# CLK_SYNTH_V2_4.net
KiCad netlist of a schematic drawn in Altium Designer
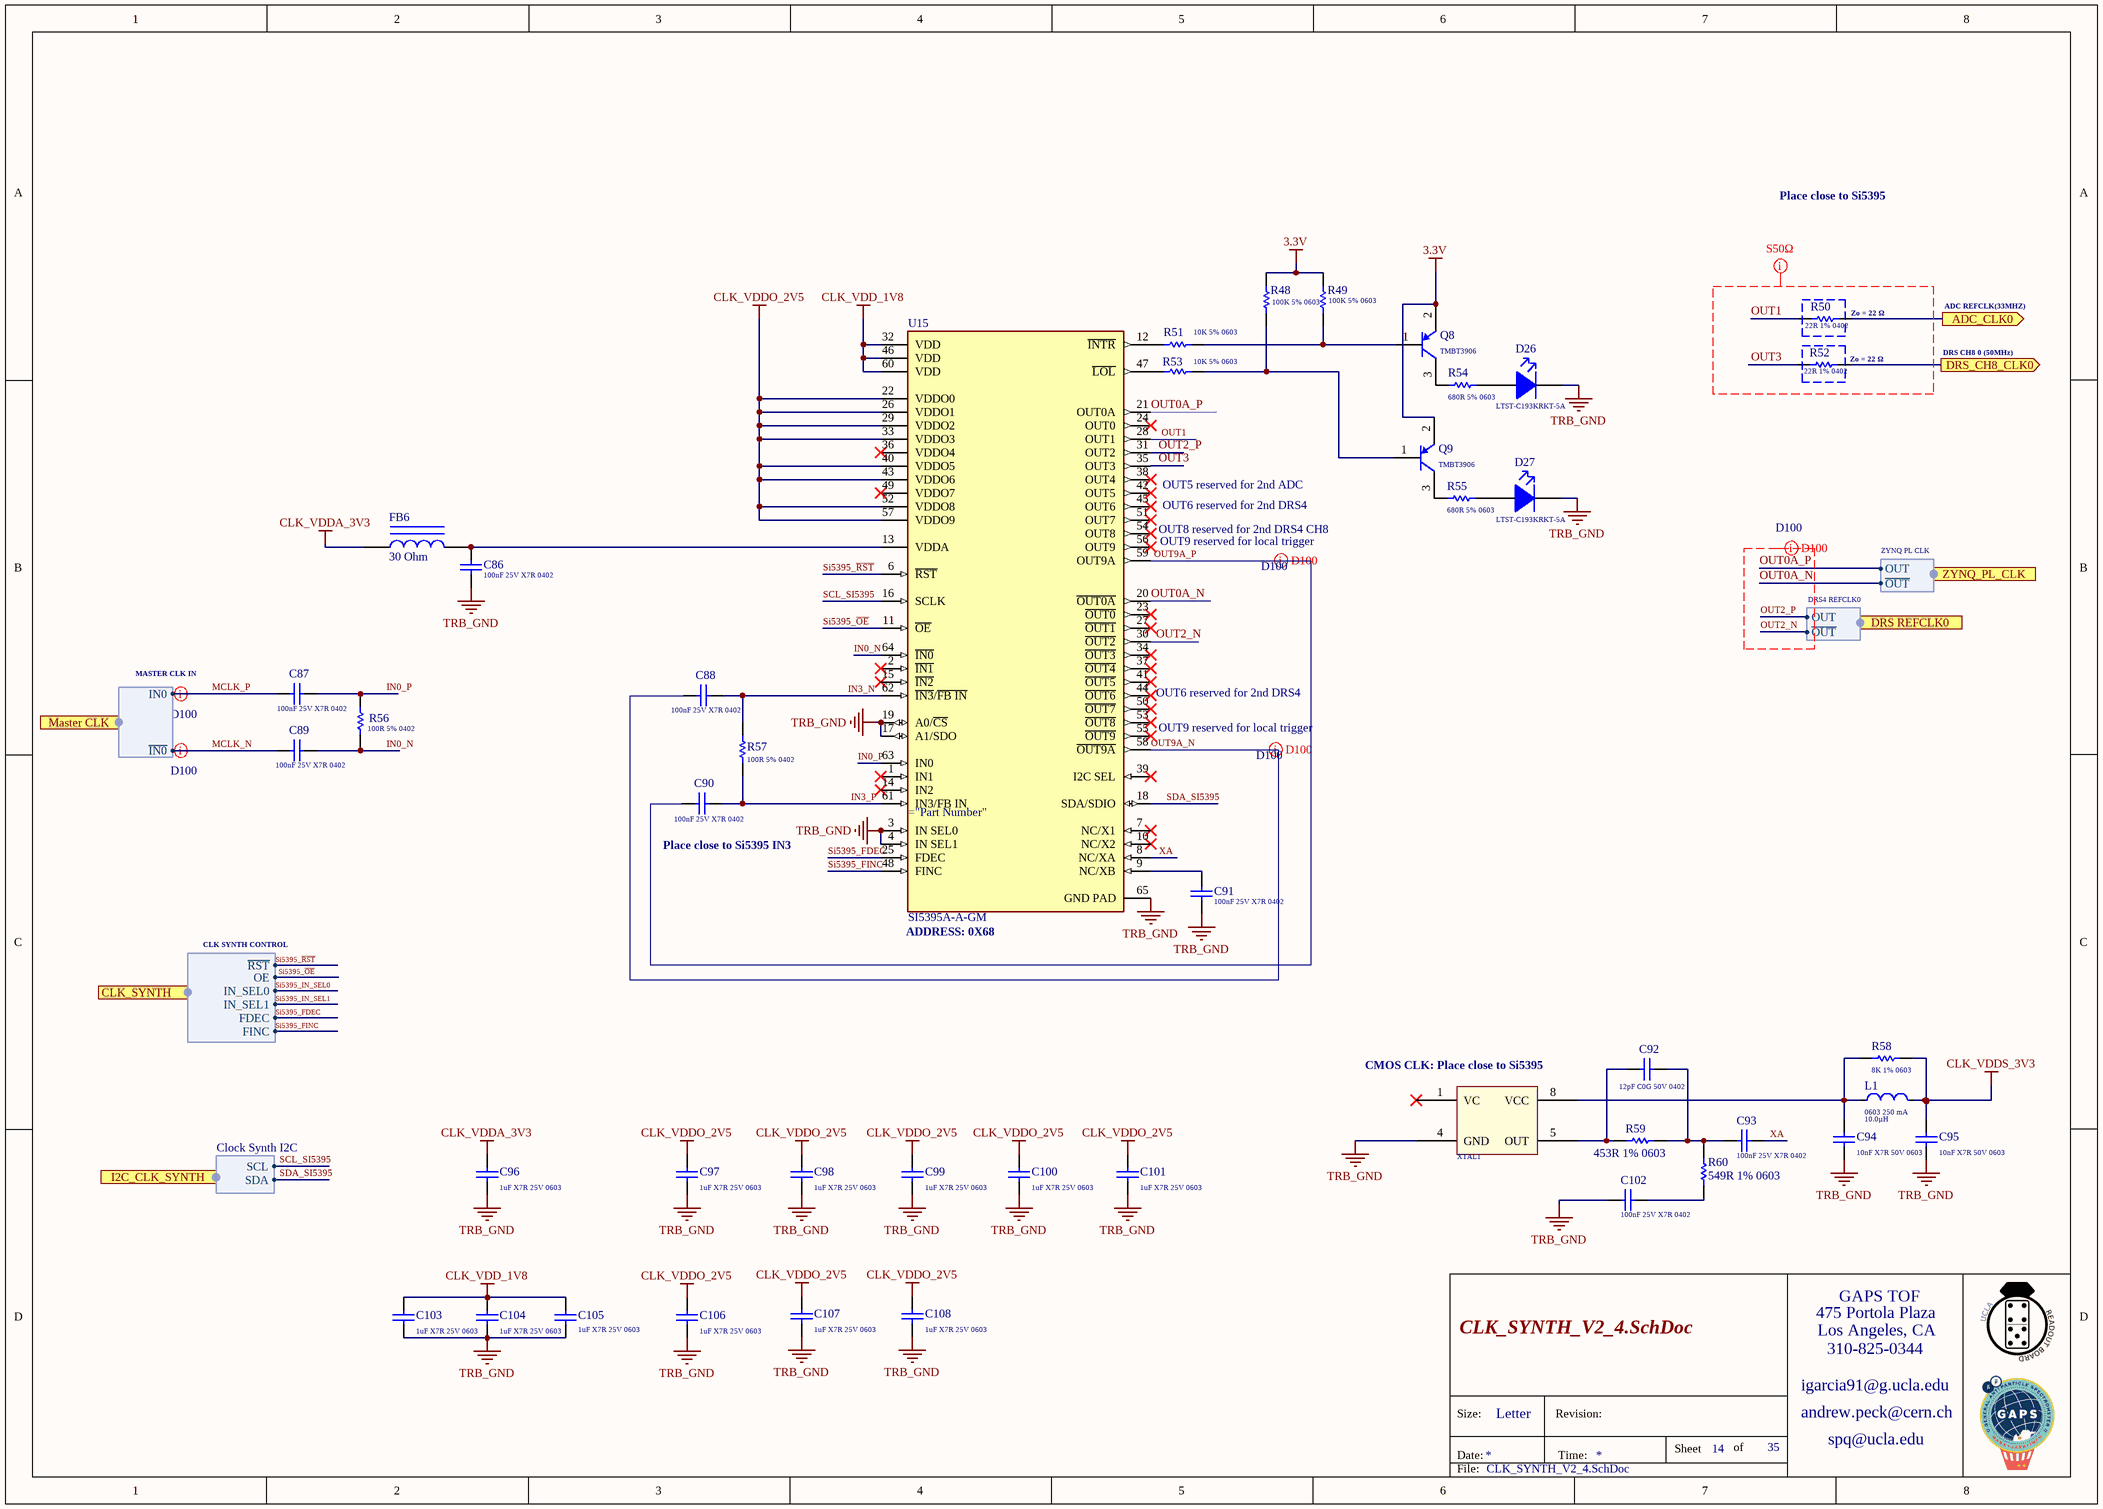
[diagram p0: CLK_SYNTH_V2_4.SchDoc]

(export (version "E")
  (design (tool "Eeschema 10.0.6"))
  (components
    (comp (ref "C86")
      (value "Cap_Taiyo_Yuden_TMK105B7104KV-FR_100nF")
      (footprint "Cap_Taiyo_Yuden_TMK105B7104KV-FR_100nF")
      (description "CAP CER 100nF 25V X7R 0402")
      (fields (field (name "CAPACITANCE") "100nF 25V X7R 0402"))
      (libsource (lib "Cap_Taiyo_Yuden_TMK105B7104KV-FR_100nF") (part "Cap_Taiyo_Yuden_TMK105B7104KV-FR_100nF"))
    )
    (comp (ref "C87")
      (value "Cap_Taiyo_Yuden_TMK105B7104KV-FR_100nF")
      (footprint "Cap_Taiyo_Yuden_TMK105B7104KV-FR_100nF")
      (description "CAP CER 100nF 25V X7R 0402")
      (fields (field (name "CAPACITANCE") "100nF 25V X7R 0402"))
      (libsource (lib "Cap_Taiyo_Yuden_TMK105B7104KV-FR_100nF") (part "Cap_Taiyo_Yuden_TMK105B7104KV-FR_100nF"))
    )
    (comp (ref "C88")
      (value "Cap_Taiyo_Yuden_TMK105B7104KV-FR_100nF")
      (footprint "Cap_Taiyo_Yuden_TMK105B7104KV-FR_100nF")
      (description "CAP CER 100nF 25V X7R 0402")
      (fields (field (name "CAPACITANCE") "100nF 25V X7R 0402"))
      (libsource (lib "Cap_Taiyo_Yuden_TMK105B7104KV-FR_100nF") (part "Cap_Taiyo_Yuden_TMK105B7104KV-FR_100nF"))
    )
    (comp (ref "C89")
      (value "Cap_Taiyo_Yuden_TMK105B7104KV-FR_100nF")
      (footprint "Cap_Taiyo_Yuden_TMK105B7104KV-FR_100nF")
      (description "CAP CER 100nF 25V X7R 0402")
      (fields (field (name "CAPACITANCE") "100nF 25V X7R 0402"))
      (libsource (lib "Cap_Taiyo_Yuden_TMK105B7104KV-FR_100nF") (part "Cap_Taiyo_Yuden_TMK105B7104KV-FR_100nF"))
    )
    (comp (ref "C90")
      (value "Cap_Taiyo_Yuden_TMK105B7104KV-FR_100nF")
      (footprint "Cap_Taiyo_Yuden_TMK105B7104KV-FR_100nF")
      (description "CAP CER 100nF 25V X7R 0402")
      (fields (field (name "CAPACITANCE") "100nF 25V X7R 0402"))
      (libsource (lib "Cap_Taiyo_Yuden_TMK105B7104KV-FR_100nF") (part "Cap_Taiyo_Yuden_TMK105B7104KV-FR_100nF"))
    )
    (comp (ref "C91")
      (value "Cap_Taiyo_Yuden_TMK105B7104KV-FR_100nF")
      (footprint "Cap_Taiyo_Yuden_TMK105B7104KV-FR_100nF")
      (description "CAP CER 100nF 25V X7R 0402")
      (fields (field (name "CAPACITANCE") "100nF 25V X7R 0402"))
      (libsource (lib "Cap_Taiyo_Yuden_TMK105B7104KV-FR_100nF") (part "Cap_Taiyo_Yuden_TMK105B7104KV-FR_100nF"))
    )
    (comp (ref "C92")
      (value "Cap_Murata_GCQ1555C1H120FB01D_12pF")
      (footprint "Cap_Murata_GCQ1555C1H120FB01D_12pF")
      (description "MLCC - SMD/SMT 0402 50VDC 12pF 1% AEC-Q200")
      (fields (field (name "CAPACITANCE") "12pF C0G 50V 0402"))
      (libsource (lib "Cap_Murata_GCQ1555C1H120FB01D_12pF") (part "Cap_Murata_GCQ1555C1H120FB01D_12pF"))
    )
    (comp (ref "C93")
      (value "Cap_Taiyo_Yuden_TMK105B7104KV-FR_100nF")
      (footprint "Cap_Taiyo_Yuden_TMK105B7104KV-FR_100nF")
      (description "CAP CER 100nF 25V X7R 0402")
      (fields (field (name "CAPACITANCE") "100nF 25V X7R 0402"))
      (libsource (lib "Cap_Taiyo_Yuden_TMK105B7104KV-FR_100nF") (part "Cap_Taiyo_Yuden_TMK105B7104KV-FR_100nF"))
    )
    (comp (ref "C94")
      (value "Cap_Kemet_C0603C103J5RACTU_eec")
      (footprint "Kemet_C0603_0")
      (description "CAP CER 10nF 50V X7R 0603")
      (fields
        (field (name "PART NUMBER") "C0603C103J5RACTU")
        (field (name "MANUFACTURER") "Kemet")
        (field (name "CAPACITANCE") "10nF X7R 50V 0603")
      )
      (libsource (lib "Cap_Kemet_C0603C103J5RACTU_10nF") (part "Cap_Kemet_C0603C103J5RACTU_eec"))
    )
    (comp (ref "C95")
      (value "Cap_Kemet_C0603C103J5RACTU_eec")
      (footprint "Kemet_C0603_0")
      (description "CAP CER 10nF 50V X7R 0603")
      (fields
        (field (name "PART NUMBER") "C0603C103J5RACTU")
        (field (name "MANUFACTURER") "Kemet")
        (field (name "CAPACITANCE") "10nF X7R 50V 0603")
      )
      (libsource (lib "Cap_Kemet_C0603C103J5RACTU_10nF") (part "Cap_Kemet_C0603C103J5RACTU_eec"))
    )
    (comp (ref "C96")
      (value "Cap_Murata_GCJ188R71E105KA01J_1uF")
      (footprint "Cap_Murata_GCJ188R71E105KA01J_1uF")
      (description "CAP CER 1uF 25V X7R 0603")
      (fields (field (name "CAPACITANCE") "1uF X7R 25V 0603"))
      (libsource (lib "Cap_Murata_GCJ188R71E105KA01J_1uF") (part "Cap_Murata_GCJ188R71E105KA01J_1uF"))
    )
    (comp (ref "C97")
      (value "Cap_Murata_GCJ188R71E105KA01J_1uF")
      (footprint "Cap_Murata_GCJ188R71E105KA01J_1uF")
      (description "CAP CER 1uF 25V X7R 0603")
      (fields (field (name "CAPACITANCE") "1uF X7R 25V 0603"))
      (libsource (lib "Cap_Murata_GCJ188R71E105KA01J_1uF") (part "Cap_Murata_GCJ188R71E105KA01J_1uF"))
    )
    (comp (ref "C98")
      (value "Cap_Murata_GCJ188R71E105KA01J_1uF")
      (footprint "Cap_Murata_GCJ188R71E105KA01J_1uF")
      (description "CAP CER 1uF 25V X7R 0603")
      (fields (field (name "CAPACITANCE") "1uF X7R 25V 0603"))
      (libsource (lib "Cap_Murata_GCJ188R71E105KA01J_1uF") (part "Cap_Murata_GCJ188R71E105KA01J_1uF"))
    )
    (comp (ref "C99")
      (value "Cap_Murata_GCJ188R71E105KA01J_1uF")
      (footprint "Cap_Murata_GCJ188R71E105KA01J_1uF")
      (description "CAP CER 1uF 25V X7R 0603")
      (fields (field (name "CAPACITANCE") "1uF X7R 25V 0603"))
      (libsource (lib "Cap_Murata_GCJ188R71E105KA01J_1uF") (part "Cap_Murata_GCJ188R71E105KA01J_1uF"))
    )
    (comp (ref "C100")
      (value "Cap_Murata_GCJ188R71E105KA01J_1uF")
      (footprint "Cap_Murata_GCJ188R71E105KA01J_1uF")
      (description "CAP CER 1uF 25V X7R 0603")
      (fields (field (name "CAPACITANCE") "1uF X7R 25V 0603"))
      (libsource (lib "Cap_Murata_GCJ188R71E105KA01J_1uF") (part "Cap_Murata_GCJ188R71E105KA01J_1uF"))
    )
    (comp (ref "C101")
      (value "Cap_Murata_GCJ188R71E105KA01J_1uF")
      (footprint "Cap_Murata_GCJ188R71E105KA01J_1uF")
      (description "CAP CER 1uF 25V X7R 0603")
      (fields (field (name "CAPACITANCE") "1uF X7R 25V 0603"))
      (libsource (lib "Cap_Murata_GCJ188R71E105KA01J_1uF") (part "Cap_Murata_GCJ188R71E105KA01J_1uF"))
    )
    (comp (ref "C102")
      (value "Cap_Taiyo_Yuden_TMK105B7104KV-FR_100nF")
      (footprint "Cap_Taiyo_Yuden_TMK105B7104KV-FR_100nF")
      (description "CAP CER 100nF 25V X7R 0402")
      (fields (field (name "CAPACITANCE") "100nF 25V X7R 0402"))
      (libsource (lib "Cap_Taiyo_Yuden_TMK105B7104KV-FR_100nF") (part "Cap_Taiyo_Yuden_TMK105B7104KV-FR_100nF"))
    )
    (comp (ref "C103")
      (value "Cap_Murata_GCJ188R71E105KA01J_1uF")
      (footprint "Cap_Murata_GCJ188R71E105KA01J_1uF")
      (description "CAP CER 1uF 25V X7R 0603")
      (fields (field (name "CAPACITANCE") "1uF X7R 25V 0603"))
      (libsource (lib "Cap_Murata_GCJ188R71E105KA01J_1uF") (part "Cap_Murata_GCJ188R71E105KA01J_1uF"))
    )
    (comp (ref "C104")
      (value "Cap_Murata_GCJ188R71E105KA01J_1uF")
      (footprint "Cap_Murata_GCJ188R71E105KA01J_1uF")
      (description "CAP CER 1uF 25V X7R 0603")
      (fields (field (name "CAPACITANCE") "1uF X7R 25V 0603"))
      (libsource (lib "Cap_Murata_GCJ188R71E105KA01J_1uF") (part "Cap_Murata_GCJ188R71E105KA01J_1uF"))
    )
    (comp (ref "C105")
      (value "Cap_Murata_GCJ188R71E105KA01J_1uF")
      (footprint "Cap_Murata_GCJ188R71E105KA01J_1uF")
      (description "CAP CER 1uF 25V X7R 0603")
      (fields (field (name "CAPACITANCE") "1uF X7R 25V 0603"))
      (libsource (lib "Cap_Murata_GCJ188R71E105KA01J_1uF") (part "Cap_Murata_GCJ188R71E105KA01J_1uF"))
    )
    (comp (ref "C106")
      (value "Cap_Murata_GCJ188R71E105KA01J_1uF")
      (footprint "Cap_Murata_GCJ188R71E105KA01J_1uF")
      (description "CAP CER 1uF 25V X7R 0603")
      (fields (field (name "CAPACITANCE") "1uF X7R 25V 0603"))
      (libsource (lib "Cap_Murata_GCJ188R71E105KA01J_1uF") (part "Cap_Murata_GCJ188R71E105KA01J_1uF"))
    )
    (comp (ref "C107")
      (value "Cap_Murata_GCJ188R71E105KA01J_1uF")
      (footprint "Cap_Murata_GCJ188R71E105KA01J_1uF")
      (description "CAP CER 1uF 25V X7R 0603")
      (fields (field (name "CAPACITANCE") "1uF X7R 25V 0603"))
      (libsource (lib "Cap_Murata_GCJ188R71E105KA01J_1uF") (part "Cap_Murata_GCJ188R71E105KA01J_1uF"))
    )
    (comp (ref "C108")
      (value "Cap_Murata_GCJ188R71E105KA01J_1uF")
      (footprint "Cap_Murata_GCJ188R71E105KA01J_1uF")
      (description "CAP CER 1uF 25V X7R 0603")
      (fields (field (name "CAPACITANCE") "1uF X7R 25V 0603"))
      (libsource (lib "Cap_Murata_GCJ188R71E105KA01J_1uF") (part "Cap_Murata_GCJ188R71E105KA01J_1uF"))
    )
    (comp (ref "D26")
      (value "LTST-C193KRKT-5A")
      (footprint "Led_Lite-On_LTST-C193KGKT-5A_Red")
      (description "Standard LEDs - SMD Red 470nm 28mcd 20mA")
      (fields (field (name "SERIES") "LTST-C193KRKT-5A"))
      (libsource (lib "Led_Lite-On_LTST-C193KGKT-5A_Red") (part "Led_Lite-On_LTST-C193KGKT-5A_Red"))
    )
    (comp (ref "D27")
      (value "LTST-C193KRKT-5A")
      (footprint "Led_Lite-On_LTST-C193KGKT-5A_Red")
      (description "Standard LEDs - SMD Red 470nm 28mcd 20mA")
      (fields (field (name "SERIES") "LTST-C193KRKT-5A"))
      (libsource (lib "Led_Lite-On_LTST-C193KGKT-5A_Red") (part "Led_Lite-On_LTST-C193KGKT-5A_Red"))
    )
    (comp (ref "FB6")
      (value "30 Ohm")
      (footprint "Feb_MURATA_BLM15AX300SZ1D_30")
      (description "Feb SMD 30 OHM 25% 3/4W 0402")
      (libsource (lib "Feb_MURATA_BLM15AX300SZ1D_30") (part "Feb_MURATA_BLM15AX300SZ1D_30"))
    )
    (comp (ref "L1")
      (value "0603 250 mA")
      (footprint "TDK_MLZ1608M100WT_0")
      (description "IND 10µH Shielded Multilayer Inductor 250mA 1.365 Ohm Max 0603 (1608 Metric)")
      (fields
        (field (name "PART NUMBER") "MLZ1608M100WT")
        (field (name "MANUFACTURER") "TDK")
        (field (name "INDUCTANCE") "10.0µH")
      )
      (libsource (lib "Ind_TDK_MLZ1608M100WT_10uH") (part "Ind_TDK_MLZ1608M100WT_eec"))
    )
    (comp (ref "Q8")
      (value "BJT_PNP_Toshiba_TMBT3906")
      (footprint "BJT_PNP_Toshiba_TMBT3906")
      (description "Bipolar Transistors - BJT Transistor for Low Freq. Amplification")
      (fields (field (name "SERIES") "TMBT3906") (field (name "MANUFACTURER") "Toshiba"))
      (libsource (lib "BJT_PNP_Toshiba_TMBT3906") (part "BJT_PNP_Toshiba_TMBT3906"))
    )
    (comp (ref "Q9")
      (value "BJT_PNP_Toshiba_TMBT3906")
      (footprint "BJT_PNP_Toshiba_TMBT3906")
      (description "Bipolar Transistors - BJT Transistor for Low Freq. Amplification")
      (fields (field (name "SERIES") "TMBT3906") (field (name "MANUFACTURER") "Toshiba"))
      (libsource (lib "BJT_PNP_Toshiba_TMBT3906") (part "BJT_PNP_Toshiba_TMBT3906"))
    )
    (comp (ref "R48")
      (value "100K 5% 0603")
      (footprint "RESC0603(1608)_N")
      (description "100K 0.1W 5% 0603 (1608 Metric)  SMD")
      (fields (field (name "TOLERANCE") "5 %") (field (name "POWER") "0.1 W"))
      (libsource (lib "Altium Content Vault") (part "RES"))
    )
    (comp (ref "R49")
      (value "100K 5% 0603")
      (footprint "RESC0603(1608)_N")
      (description "100K 0.1W 5% 0603 (1608 Metric)  SMD")
      (fields (field (name "TOLERANCE") "5 %") (field (name "POWER") "0.1 W"))
      (libsource (lib "Altium Content Vault") (part "RES"))
    )
    (comp (ref "R50")
      (value "22R 1% 0402")
      (footprint "RESC0402(1005)_L")
      (description "22R 0.063W 1% 0402 (1005 Metric)  SMD")
      (fields (field (name "TOLERANCE") "1 %") (field (name "POWER") "0.063 W"))
      (libsource (lib "Altium Content Vault") (part "RES"))
    )
    (comp (ref "R51")
      (value "10K 5% 0603")
      (footprint "RESC0603(1608)_L")
      (description "10K 0.1W 5% 0603 (1608 Metric)  SMD")
      (fields (field (name "TOLERANCE") "5 %") (field (name "POWER") "0.1 W"))
      (libsource (lib "Altium Content Vault") (part "RES"))
    )
    (comp (ref "R52")
      (value "22R 1% 0402")
      (footprint "RESC0402(1005)_L")
      (description "22R 0.063W 1% 0402 (1005 Metric)  SMD")
      (fields (field (name "TOLERANCE") "1 %") (field (name "POWER") "0.063 W"))
      (libsource (lib "Altium Content Vault") (part "RES"))
    )
    (comp (ref "R53")
      (value "10K 5% 0603")
      (footprint "RESC0603(1608)_L")
      (description "10K 0.1W 5% 0603 (1608 Metric)  SMD")
      (fields (field (name "TOLERANCE") "5 %") (field (name "POWER") "0.1 W"))
      (libsource (lib "Altium Content Vault") (part "RES"))
    )
    (comp (ref "R54")
      (value "680R 5% 0603")
      (footprint "RESC0603(1608)_L")
      (description "680R 0.1W 5% 0603 (1608 Metric)  SMD")
      (fields (field (name "TOLERANCE") "5 %") (field (name "POWER") "0.1 W"))
      (libsource (lib "Altium Content Vault") (part "RES"))
    )
    (comp (ref "R55")
      (value "680R 5% 0603")
      (footprint "RESC0603(1608)_L")
      (description "680R 0.1W 5% 0603 (1608 Metric)  SMD")
      (fields (field (name "TOLERANCE") "5 %") (field (name "POWER") "0.1 W"))
      (libsource (lib "Altium Content Vault") (part "RES"))
    )
    (comp (ref "R56")
      (value "100R 5% 0402")
      (footprint "RESC0402(1005)_L")
      (description "100R 0.063W 5% 0402 (1005 Metric)  SMD")
      (fields (field (name "TOLERANCE") "5 %") (field (name "POWER") "0.063 W"))
      (libsource (lib "Altium Content Vault") (part "RES"))
    )
    (comp (ref "R57")
      (value "100R 5% 0402")
      (footprint "RESC0402(1005)_L")
      (description "100R 0.063W 5% 0402 (1005 Metric)  SMD")
      (fields (field (name "TOLERANCE") "5 %") (field (name "POWER") "0.063 W"))
      (libsource (lib "Altium Content Vault") (part "RES"))
    )
    (comp (ref "R58")
      (value "8K 1% 0603")
      (footprint "Res_Yageo_RT0603BRE078KL_8K")
      (description "8K 0.1W 1% 0603 (1608 Metric)  SMD")
      (libsource (lib "Res_Yageo_RT0603BRE078KL_8K") (part "Res_Yageo_RT0603BRE078KL_8K"))
    )
    (comp (ref "R59")
      (value "453R 1% 0603")
      (footprint "RESC1608X55X30NL15T15")
      (description "ERJ-3EKF4530V")
      (fields (field (name "MANUFACTURER") "Panasonic"))
      (libsource (lib "Altium Content Vault") (part "RES"))
    )
    (comp (ref "R60")
      (value "549R 1% 0603")
      (footprint "RESC1608X55X30NL15T15")
      (description "ERJ-3EKF5490V")
      (fields (field (name "MANUFACTURER") "Panasonic"))
      (libsource (lib "Altium Content Vault") (part "RES"))
    )
    (comp (ref "U15")
      (value "IC_Silicon_Laboratories_ SI5395A-A-GM_CLK")
      (footprint "Si5395")
      (fields (field (name "SERIES") "SI5395A-A-GM"))
      (libsource (lib "SI5395A-A-GM") (part "IC_Silicon_Laboratories_ SI5395A-A-GM_CLK"))
    )
    (comp (ref "XTAL1")
      (value "TCXO_Murata_XTCLH50M000CHJA3P0_50MHz")
      (footprint "TCXO_Murata_XTCLH50M000CHJA3P0_50MHz")
      (description "TCXO Oscillators 50MHz 5x3.2x1.5mm 0.2ppm max Crystal")
      (libsource (lib "TCXO_Murata_XTCLH50M000CHJA3P0_50MHz") (part "TCXO_Murata_XTCLH50M000CHJA3P0_50MHz"))
    )
  )
  (nets
    (net (code "13") (name "/ADC_CLK0") (class "Default")
      (node (ref "R50") (pin "1") (pinfunction "1_1") (pintype "passive"))
    )
    (net (code "14") (name "/DRS_CH8_CLK0") (class "Default")
      (node (ref "R52") (pin "1") (pinfunction "1_1") (pintype "passive"))
    )
    (net (code "15") (name "/IN0_N") (class "Default")
      (node (ref "C89") (pin "2") (pinfunction "2_2") (pintype "passive"))
      (node (ref "R56") (pin "1") (pinfunction "1_1") (pintype "passive"))
      (node (ref "U15") (pin "64") (pinfunction "~{IN0}_64") (pintype "input"))
    )
    (net (code "16") (name "/IN0_P") (class "Default")
      (node (ref "C87") (pin "2") (pinfunction "2_2") (pintype "passive"))
      (node (ref "R56") (pin "2") (pinfunction "2_2") (pintype "passive"))
      (node (ref "U15") (pin "63") (pinfunction "IN0_63") (pintype "input"))
    )
    (net (code "17") (name "/IN3_N") (class "Default")
      (node (ref "C88") (pin "2") (pinfunction "2_2") (pintype "passive"))
      (node (ref "R57") (pin "2") (pinfunction "2_2") (pintype "passive"))
      (node (ref "U15") (pin "62") (pinfunction "~{IN3}/~{FB_IN}_62") (pintype "input"))
    )
    (net (code "18") (name "/IN3_P") (class "Default")
      (node (ref "C90") (pin "2") (pinfunction "2_2") (pintype "passive"))
      (node (ref "R57") (pin "1") (pinfunction "1_1") (pintype "passive"))
      (node (ref "U15") (pin "61") (pinfunction "IN3/FB_IN_61") (pintype "input"))
    )
    (net (code "19") (name "/MCLK_N") (class "Default")
      (node (ref "C89") (pin "1") (pinfunction "1_1") (pintype "passive"))
    )
    (net (code "20") (name "/MCLK_P") (class "Default")
      (node (ref "C87") (pin "1") (pinfunction "1_1") (pintype "passive"))
    )
    (net (code "21") (name "/OUT0A_N") (class "Default")
      (node (ref "U15") (pin "20") (pinfunction "~{OUT0A}_20") (pintype "output"))
    )
    (net (code "22") (name "/OUT0A_P") (class "Default")
      (node (ref "U15") (pin "21") (pinfunction "OUT0A_21") (pintype "output"))
    )
    (net (code "23") (name "/OUT1") (class "Default")
      (node (ref "R50") (pin "2") (pinfunction "2_2") (pintype "passive"))
      (node (ref "U15") (pin "28") (pinfunction "OUT1_28") (pintype "output"))
    )
    (net (code "24") (name "/OUT2_N") (class "Default")
      (node (ref "U15") (pin "30") (pinfunction "~{OUT2}_30") (pintype "output"))
    )
    (net (code "25") (name "/OUT2_P") (class "Default")
      (node (ref "U15") (pin "31") (pinfunction "OUT2_31") (pintype "output"))
    )
    (net (code "26") (name "/OUT3") (class "Default")
      (node (ref "R52") (pin "2") (pinfunction "2_2") (pintype "passive"))
      (node (ref "U15") (pin "35") (pinfunction "OUT3_35") (pintype "output"))
    )
    (net (code "27") (name "/OUT9A_N") (class "Default")
      (node (ref "C88") (pin "1") (pinfunction "1_1") (pintype "passive"))
      (node (ref "U15") (pin "58") (pinfunction "~{OUT9A}_58") (pintype "output"))
    )
    (net (code "28") (name "/OUT9A_P") (class "Default")
      (node (ref "C90") (pin "1") (pinfunction "1_1") (pintype "passive"))
      (node (ref "U15") (pin "59") (pinfunction "OUT9A_59") (pintype "output"))
    )
    (net (code "29") (name "/SCL_SI5395") (class "Default")
      (node (ref "U15") (pin "16") (pinfunction "SCLK_16") (pintype "input"))
    )
    (net (code "30") (name "/SDA_SI5395") (class "Default")
      (node (ref "U15") (pin "18") (pinfunction "SDA/SDIO_18") (pintype "bidirectional"))
    )
    (net (code "31") (name "/Si5395_FDEC") (class "Default")
      (node (ref "U15") (pin "25") (pinfunction "FDEC_25") (pintype "input"))
    )
    (net (code "32") (name "/Si5395_FINC") (class "Default")
      (node (ref "U15") (pin "48") (pinfunction "FINC_48") (pintype "input"))
    )
    (net (code "35") (name "/Si5395_~{OE}") (class "Default")
      (node (ref "U15") (pin "11") (pinfunction "~{OE}_11") (pintype "input"))
    )
    (net (code "36") (name "/Si5395_~{RST}") (class "Default")
      (node (ref "U15") (pin "6") (pinfunction "~{RST}_6") (pintype "input"))
    )
    (net (code "37") (name "/XA") (class "Default")
      (node (ref "C93") (pin "2") (pinfunction "2_2") (pintype "passive"))
      (node (ref "U15") (pin "8") (pinfunction "NC/XA_8") (pintype "input"))
    )
    (net (code "43") (name "3.3V") (class "Default")
      (node (ref "Q8") (pin "2") (pinfunction "E_2") (pintype "passive"))
      (node (ref "Q9") (pin "2") (pinfunction "E_2") (pintype "passive"))
      (node (ref "R48") (pin "2") (pinfunction "2_2") (pintype "passive"))
      (node (ref "R49") (pin "2") (pinfunction "2_2") (pintype "passive"))
    )
    (net (code "44") (name "CLK_VDDA_3V3") (class "Default")
      (node (ref "C96") (pin "2") (pinfunction "2_2") (pintype "passive"))
      (node (ref "FB6") (pin "1") (pinfunction "1_1") (pintype "passive"))
    )
    (net (code "45") (name "CLK_VDDO_2V5") (class "Default")
      (node (ref "C100") (pin "2") (pinfunction "2_2") (pintype "passive"))
      (node (ref "C101") (pin "2") (pinfunction "2_2") (pintype "passive"))
      (node (ref "C106") (pin "2") (pinfunction "2_2") (pintype "passive"))
      (node (ref "C107") (pin "2") (pinfunction "2_2") (pintype "passive"))
      (node (ref "C108") (pin "2") (pinfunction "2_2") (pintype "passive"))
      (node (ref "C97") (pin "2") (pinfunction "2_2") (pintype "passive"))
      (node (ref "C98") (pin "2") (pinfunction "2_2") (pintype "passive"))
      (node (ref "C99") (pin "2") (pinfunction "2_2") (pintype "passive"))
      (node (ref "U15") (pin "22") (pinfunction "VDDO0_22") (pintype "power_in"))
      (node (ref "U15") (pin "26") (pinfunction "VDDO1_26") (pintype "power_in"))
      (node (ref "U15") (pin "29") (pinfunction "VDDO2_29") (pintype "power_in"))
      (node (ref "U15") (pin "33") (pinfunction "VDDO3_33") (pintype "power_in"))
      (node (ref "U15") (pin "40") (pinfunction "VDDO5_40") (pintype "power_in"))
      (node (ref "U15") (pin "43") (pinfunction "VDDO6_43") (pintype "power_in"))
      (node (ref "U15") (pin "52") (pinfunction "VDDO8_52") (pintype "power_in"))
      (node (ref "U15") (pin "57") (pinfunction "VDDO9_57") (pintype "power_in"))
    )
    (net (code "46") (name "CLK_VDDS_3V3") (class "Default")
      (node (ref "C95") (pin "1") (pinfunction "1_1") (pintype "passive"))
      (node (ref "L1") (pin "2") (pinfunction "2_2") (pintype "passive"))
      (node (ref "R58") (pin "2") (pinfunction "2_2") (pintype "passive"))
    )
    (net (code "47") (name "CLK_VDD_1V8") (class "Default")
      (node (ref "C103") (pin "2") (pinfunction "2_2") (pintype "passive"))
      (node (ref "C104") (pin "2") (pinfunction "2_2") (pintype "passive"))
      (node (ref "C105") (pin "2") (pinfunction "2_2") (pintype "passive"))
      (node (ref "U15") (pin "32") (pinfunction "VDD_32") (pintype "power_in"))
      (node (ref "U15") (pin "46") (pinfunction "VDD_46") (pintype "power_in"))
      (node (ref "U15") (pin "60") (pinfunction "VDD_60") (pintype "power_in"))
    )
    (net (code "48") (name "Net-(C92-Pad1)") (class "Default")
      (node (ref "C92") (pin "1") (pinfunction "1_1") (pintype "passive"))
      (node (ref "C93") (pin "1") (pinfunction "1_1") (pintype "passive"))
      (node (ref "R59") (pin "2") (pinfunction "2_2") (pintype "passive"))
      (node (ref "R60") (pin "2") (pinfunction "2_2") (pintype "passive"))
    )
    (net (code "49") (name "Net-(C102-Pad2)") (class "Default")
      (node (ref "C102") (pin "2") (pinfunction "2_2") (pintype "passive"))
      (node (ref "R60") (pin "1") (pinfunction "1_1") (pintype "passive"))
    )
    (net (code "50") (name "Net-(D26-A)") (class "Default")
      (node (ref "D26") (pin "2") (pinfunction "A_2") (pintype "passive"))
      (node (ref "R54") (pin "2") (pinfunction "2_2") (pintype "passive"))
    )
    (net (code "51") (name "Net-(D27-A)") (class "Default")
      (node (ref "D27") (pin "2") (pinfunction "A_2") (pintype "passive"))
      (node (ref "R55") (pin "2") (pinfunction "2_2") (pintype "passive"))
    )
    (net (code "52") (name "Net-(Q8-B)") (class "Default")
      (node (ref "Q8") (pin "1") (pinfunction "B_1") (pintype "passive"))
      (node (ref "R49") (pin "1") (pinfunction "1_1") (pintype "passive"))
      (node (ref "R51") (pin "1") (pinfunction "1_1") (pintype "passive"))
    )
    (net (code "53") (name "Net-(Q8-C)") (class "Default")
      (node (ref "Q8") (pin "3") (pinfunction "C_3") (pintype "passive"))
      (node (ref "R54") (pin "1") (pinfunction "1_1") (pintype "passive"))
    )
    (net (code "54") (name "Net-(Q9-B)") (class "Default")
      (node (ref "Q9") (pin "1") (pinfunction "B_1") (pintype "passive"))
      (node (ref "R48") (pin "1") (pinfunction "1_1") (pintype "passive"))
      (node (ref "R53") (pin "1") (pinfunction "1_1") (pintype "passive"))
    )
    (net (code "55") (name "Net-(Q9-C)") (class "Default")
      (node (ref "Q9") (pin "3") (pinfunction "C_3") (pintype "passive"))
      (node (ref "R55") (pin "1") (pinfunction "1_1") (pintype "passive"))
    )
    (net (code "56") (name "Net-(U15-NC{slash}XB)") (class "Default")
      (node (ref "C91") (pin "2") (pinfunction "2_2") (pintype "passive"))
      (node (ref "U15") (pin "9") (pinfunction "NC/XB_9") (pintype "input"))
    )
    (net (code "57") (name "Net-(U15-VDDA)") (class "Default")
      (node (ref "C86") (pin "2") (pinfunction "2_2") (pintype "passive"))
      (node (ref "FB6") (pin "2") (pinfunction "2_2") (pintype "passive"))
      (node (ref "U15") (pin "13") (pinfunction "VDDA_13") (pintype "power_in"))
    )
    (net (code "58") (name "Net-(U15-~{INTR})") (class "Default")
      (node (ref "R51") (pin "2") (pinfunction "2_2") (pintype "passive"))
      (node (ref "U15") (pin "12") (pinfunction "~{INTR}_12") (pintype "output"))
    )
    (net (code "59") (name "Net-(U15-~{LOL})") (class "Default")
      (node (ref "R53") (pin "2") (pinfunction "2_2") (pintype "passive"))
      (node (ref "U15") (pin "47") (pinfunction "~{LOL}_47") (pintype "output"))
    )
    (net (code "60") (name "Net-(XTAL1-OUT)") (class "Default")
      (node (ref "C92") (pin "2") (pinfunction "2_2") (pintype "passive"))
      (node (ref "R59") (pin "1") (pinfunction "1_1") (pintype "passive"))
      (node (ref "XTAL1") (pin "5") (pinfunction "OUT_5") (pintype "passive"))
    )
    (net (code "61") (name "Net-(XTAL1-VCC)") (class "Default")
      (node (ref "C94") (pin "1") (pinfunction "1_1") (pintype "passive"))
      (node (ref "L1") (pin "1") (pinfunction "1_1") (pintype "passive"))
      (node (ref "R58") (pin "1") (pinfunction "1_1") (pintype "passive"))
      (node (ref "XTAL1") (pin "8") (pinfunction "VCC_8") (pintype "passive"))
    )
    (net (code "62") (name "TRB_GND") (class "Default")
      (node (ref "C100") (pin "1") (pinfunction "1_1") (pintype "passive"))
      (node (ref "C101") (pin "1") (pinfunction "1_1") (pintype "passive"))
      (node (ref "C102") (pin "1") (pinfunction "1_1") (pintype "passive"))
      (node (ref "C103") (pin "1") (pinfunction "1_1") (pintype "passive"))
      (node (ref "C104") (pin "1") (pinfunction "1_1") (pintype "passive"))
      (node (ref "C105") (pin "1") (pinfunction "1_1") (pintype "passive"))
      (node (ref "C106") (pin "1") (pinfunction "1_1") (pintype "passive"))
      (node (ref "C107") (pin "1") (pinfunction "1_1") (pintype "passive"))
      (node (ref "C108") (pin "1") (pinfunction "1_1") (pintype "passive"))
      (node (ref "C86") (pin "1") (pinfunction "1_1") (pintype "passive"))
      (node (ref "C91") (pin "1") (pinfunction "1_1") (pintype "passive"))
      (node (ref "C94") (pin "2") (pinfunction "2_2") (pintype "passive"))
      (node (ref "C95") (pin "2") (pinfunction "2_2") (pintype "passive"))
      (node (ref "C96") (pin "1") (pinfunction "1_1") (pintype "passive"))
      (node (ref "C97") (pin "1") (pinfunction "1_1") (pintype "passive"))
      (node (ref "C98") (pin "1") (pinfunction "1_1") (pintype "passive"))
      (node (ref "C99") (pin "1") (pinfunction "1_1") (pintype "passive"))
      (node (ref "D26") (pin "1") (pinfunction "K_1") (pintype "passive"))
      (node (ref "D27") (pin "1") (pinfunction "K_1") (pintype "passive"))
      (node (ref "U15") (pin "17") (pinfunction "A1/SDO_17") (pintype "bidirectional"))
      (node (ref "U15") (pin "19") (pinfunction "A0/~{CS}_19") (pintype "bidirectional"))
      (node (ref "U15") (pin "3") (pinfunction "IN_SEL0_3") (pintype "input"))
      (node (ref "U15") (pin "4") (pinfunction "IN_SEL1_4") (pintype "input"))
      (node (ref "U15") (pin "65") (pinfunction "GND_PAD_65") (pintype "power_in"))
      (node (ref "XTAL1") (pin "4") (pinfunction "GND_4") (pintype "passive"))
    )
    (net (code "63") (name "unconnected-(U15-I2C_SEL-Pad39)") (class "Default")
      (node (ref "U15") (pin "39") (pinfunction "I2C_SEL_39") (pintype "input+no_connect"))
    )
    (net (code "64") (name "unconnected-(U15-IN1-Pad1)") (class "Default")
      (node (ref "U15") (pin "1") (pinfunction "IN1_1") (pintype "input+no_connect"))
    )
    (net (code "65") (name "unconnected-(U15-IN2-Pad14)") (class "Default")
      (node (ref "U15") (pin "14") (pinfunction "IN2_14") (pintype "input+no_connect"))
    )
    (net (code "66") (name "unconnected-(U15-NC{slash}X1-Pad7)") (class "Default")
      (node (ref "U15") (pin "7") (pinfunction "NC/X1_7") (pintype "input+no_connect"))
    )
    (net (code "67") (name "unconnected-(U15-NC{slash}X2-Pad10)") (class "Default")
      (node (ref "U15") (pin "10") (pinfunction "NC/X2_10") (pintype "input+no_connect"))
    )
    (net (code "68") (name "unconnected-(U15-OUT0-Pad24)") (class "Default")
      (node (ref "U15") (pin "24") (pinfunction "OUT0_24") (pintype "output+no_connect"))
    )
    (net (code "69") (name "unconnected-(U15-OUT4-Pad38)") (class "Default")
      (node (ref "U15") (pin "38") (pinfunction "OUT4_38") (pintype "output+no_connect"))
    )
    (net (code "70") (name "unconnected-(U15-OUT5-Pad42)") (class "Default")
      (node (ref "U15") (pin "42") (pinfunction "OUT5_42") (pintype "output+no_connect"))
    )
    (net (code "71") (name "unconnected-(U15-OUT6-Pad45)") (class "Default")
      (node (ref "U15") (pin "45") (pinfunction "OUT6_45") (pintype "output+no_connect"))
    )
    (net (code "72") (name "unconnected-(U15-OUT7-Pad51)") (class "Default")
      (node (ref "U15") (pin "51") (pinfunction "OUT7_51") (pintype "output+no_connect"))
    )
    (net (code "73") (name "unconnected-(U15-OUT8-Pad54)") (class "Default")
      (node (ref "U15") (pin "54") (pinfunction "OUT8_54") (pintype "output+no_connect"))
    )
    (net (code "74") (name "unconnected-(U15-OUT9-Pad56)") (class "Default")
      (node (ref "U15") (pin "56") (pinfunction "OUT9_56") (pintype "output+no_connect"))
    )
    (net (code "75") (name "unconnected-(U15-VDDO4-Pad36)") (class "Default")
      (node (ref "U15") (pin "36") (pinfunction "VDDO4_36") (pintype "power_in+no_connect"))
    )
    (net (code "76") (name "unconnected-(U15-VDDO7-Pad49)") (class "Default")
      (node (ref "U15") (pin "49") (pinfunction "VDDO7_49") (pintype "power_in+no_connect"))
    )
    (net (code "77") (name "unconnected-(U15-~{IN1}-Pad2)") (class "Default")
      (node (ref "U15") (pin "2") (pinfunction "~{IN1}_2") (pintype "input+no_connect"))
    )
    (net (code "78") (name "unconnected-(U15-~{IN2}-Pad15)") (class "Default")
      (node (ref "U15") (pin "15") (pinfunction "~{IN2}_15") (pintype "input+no_connect"))
    )
    (net (code "79") (name "unconnected-(U15-~{OUT0}-Pad23)") (class "Default")
      (node (ref "U15") (pin "23") (pinfunction "~{OUT0}_23") (pintype "output+no_connect"))
    )
    (net (code "80") (name "unconnected-(U15-~{OUT1}-Pad27)") (class "Default")
      (node (ref "U15") (pin "27") (pinfunction "~{OUT1}_27") (pintype "output+no_connect"))
    )
    (net (code "81") (name "unconnected-(U15-~{OUT3}-Pad34)") (class "Default")
      (node (ref "U15") (pin "34") (pinfunction "~{OUT3}_34") (pintype "output+no_connect"))
    )
    (net (code "82") (name "unconnected-(U15-~{OUT4}-Pad37)") (class "Default")
      (node (ref "U15") (pin "37") (pinfunction "~{OUT4}_37") (pintype "output+no_connect"))
    )
    (net (code "83") (name "unconnected-(U15-~{OUT5}-Pad41)") (class "Default")
      (node (ref "U15") (pin "41") (pinfunction "~{OUT5}_41") (pintype "output+no_connect"))
    )
    (net (code "84") (name "unconnected-(U15-~{OUT6}-Pad44)") (class "Default")
      (node (ref "U15") (pin "44") (pinfunction "~{OUT6}_44") (pintype "output+no_connect"))
    )
    (net (code "85") (name "unconnected-(U15-~{OUT7}-Pad50)") (class "Default")
      (node (ref "U15") (pin "50") (pinfunction "~{OUT7}_50") (pintype "output+no_connect"))
    )
    (net (code "86") (name "unconnected-(U15-~{OUT8}-Pad53)") (class "Default")
      (node (ref "U15") (pin "53") (pinfunction "~{OUT8}_53") (pintype "output+no_connect"))
    )
    (net (code "87") (name "unconnected-(U15-~{OUT9}-Pad55)") (class "Default")
      (node (ref "U15") (pin "55") (pinfunction "~{OUT9}_55") (pintype "output+no_connect"))
    )
    (net (code "88") (name "unconnected-(XTAL1-VC-Pad1)") (class "Default")
      (node (ref "XTAL1") (pin "1") (pinfunction "VC_1") (pintype "passive+no_connect"))
    )
  )
)
